# Ohmmeter_Design.net
KiCad netlist of a schematic drawn in Altium Designer
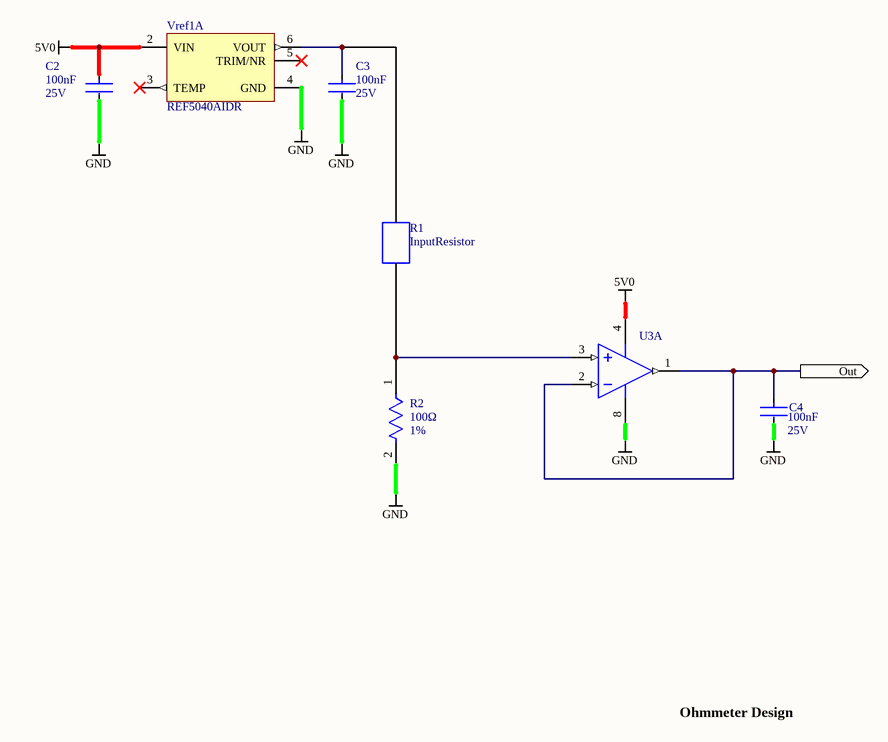
[diagram p0: Ohmmeter Design.SchDoc]

(export (version "E")
  (design (tool "Eeschema 10.0.6"))
  (components
    (comp (ref "C2")
      (value "0.1 uF")
      (footprint "FP-CL278-IPC_C")
      (description "Cap Ceramic 100nF 25V X5R ±10% SMD 0402 +85°C Paper T/R")
      (fields
        (field (name "VOLTAGE") "25V")
        (field (name "TOLERANCE") "10%")
        (field (name "CAPACITANCE") "100nF")
      )
      (libsource (lib "Altium Content Vault") (part "b4654b650e69147ec39a6b967a45e02"))
    )
    (comp (ref "C3")
      (value "0.1uF")
      (footprint "FP-CL278-IPC_C")
      (description "Cap Ceramic 100nF 25V X5R ±10% SMD 0402 +85°C Paper T/R")
      (fields
        (field (name "VOLTAGE") "25V")
        (field (name "TOLERANCE") "10%")
        (field (name "CAPACITANCE") "100nF")
      )
      (libsource (lib "Altium Content Vault") (part "b4654b650e69147ec39a6b967a45e02"))
    )
    (comp (ref "C4")
      (value "CL05A104KA5NNNC")
      (footprint "FP-CL278-IPC_C")
      (description "Cap Ceramic 100nF 25V X5R ±10% SMD 0402 +85°C Paper T/R")
      (fields
        (field (name "VOLTAGE") "25V")
        (field (name "TOLERANCE") "10%")
        (field (name "CAPACITANCE") "100nF")
      )
      (libsource (lib "Altium Content Vault") (part "b4654b650e69147ec39a6b967a45e02"))
    )
    (comp (ref "R1")
      (value "InputResistor")
      (footprint "UserInputResistor")
      (libsource (lib "ECEN215LabKit_Library") (part "InputResistor"))
    )
    (comp (ref "R2")
      (value "100Ω")
      (footprint "FP-ERJ1GN-MFG")
      (description "RES SMD 100 OHM 1% 1/20W 0201")
      (fields
        (field (name "MANUFACTURER") "Panasonic Electronic Components")
        (field (name "OCTOPART") "https://octopart.com/erj-1gnf1000c-panasonic-55419695")
        (field (name "TOLERANCE") "1%")
      )
      (libsource (lib "Altium Content Vault") (part "1029c3af85768c4190bb7ad29bc67b5"))
    )
    (comp (ref "U3")
      (value "OPA2330AIDGKR")
      (footprint "DGK0008A_M")
      (fields (field (name "MANUFACTURER") "Texas Instruments"))
      (libsource (lib "Altium Content Vault") (part "TI-OPA-8_2"))
    )
    (comp (ref "Vref1")
      (value "REF5040AIDR")
      (footprint "D0008A_M")
      (fields (field (name "MANUFACTURER") "Texas Instruments"))
      (libsource (lib "Altium Content Vault") (part "TI-REF5040D8"))
    )
  )
  (nets
    (net (code "1") (name "/Out") (class "Default")
      (node (ref "C4") (pin "1") (pinfunction "1_1") (pintype "passive"))
      (node (ref "U3") (pin "1") (pinfunction "OUT_A_1") (pintype "output"))
      (node (ref "U3") (pin "2") (pinfunction "IN_A-_2") (pintype "input"))
    )
    (net (code "2") (name "5V0") (class "Default")
      (node (ref "C2") (pin "1") (pinfunction "1_1") (pintype "passive"))
      (node (ref "U3") (pin "4") (pinfunction "V-_4") (pintype "power_in"))
      (node (ref "Vref1") (pin "2") (pinfunction "VIN_2") (pintype "power_in"))
    )
    (net (code "3") (name "GND") (class "Default")
      (node (ref "C2") (pin "2") (pinfunction "2_2") (pintype "passive"))
      (node (ref "C3") (pin "2") (pinfunction "2_2") (pintype "passive"))
      (node (ref "C4") (pin "2") (pinfunction "2_2") (pintype "passive"))
      (node (ref "R2") (pin "2") (pinfunction "2_2") (pintype "passive"))
      (node (ref "U3") (pin "8") (pinfunction "V+_8") (pintype "power_in"))
      (node (ref "Vref1") (pin "4") (pinfunction "GND_4") (pintype "power_in"))
    )
    (net (code "4") (name "Net-(U3A-IN_A+)") (class "Default")
      (node (ref "R1") (pin "1") (pintype "passive"))
      (node (ref "R2") (pin "1") (pinfunction "1_1") (pintype "passive"))
      (node (ref "U3") (pin "3") (pinfunction "IN_A+_3") (pintype "input"))
    )
    (net (code "5") (name "Net-(Vref1A-VOUT)") (class "Default")
      (node (ref "C3") (pin "1") (pinfunction "1_1") (pintype "passive"))
      (node (ref "R1") (pin "2") (pintype "passive"))
      (node (ref "Vref1") (pin "6") (pinfunction "VOUT_6") (pintype "output"))
    )
    (net (code "6") (name "unconnected-(Vref1A-TEMP-Pad3)") (class "Default")
      (node (ref "Vref1") (pin "3") (pinfunction "TEMP_3") (pintype "output+no_connect"))
    )
    (net (code "7") (name "unconnected-(Vref1A-TRIM{slash}NR-Pad5)") (class "Default")
      (node (ref "Vref1") (pin "5") (pinfunction "TRIM/NR_5") (pintype "passive+no_connect"))
    )
  )
)
